# Connectors.net
KiCad netlist of a schematic drawn in Altium Designer
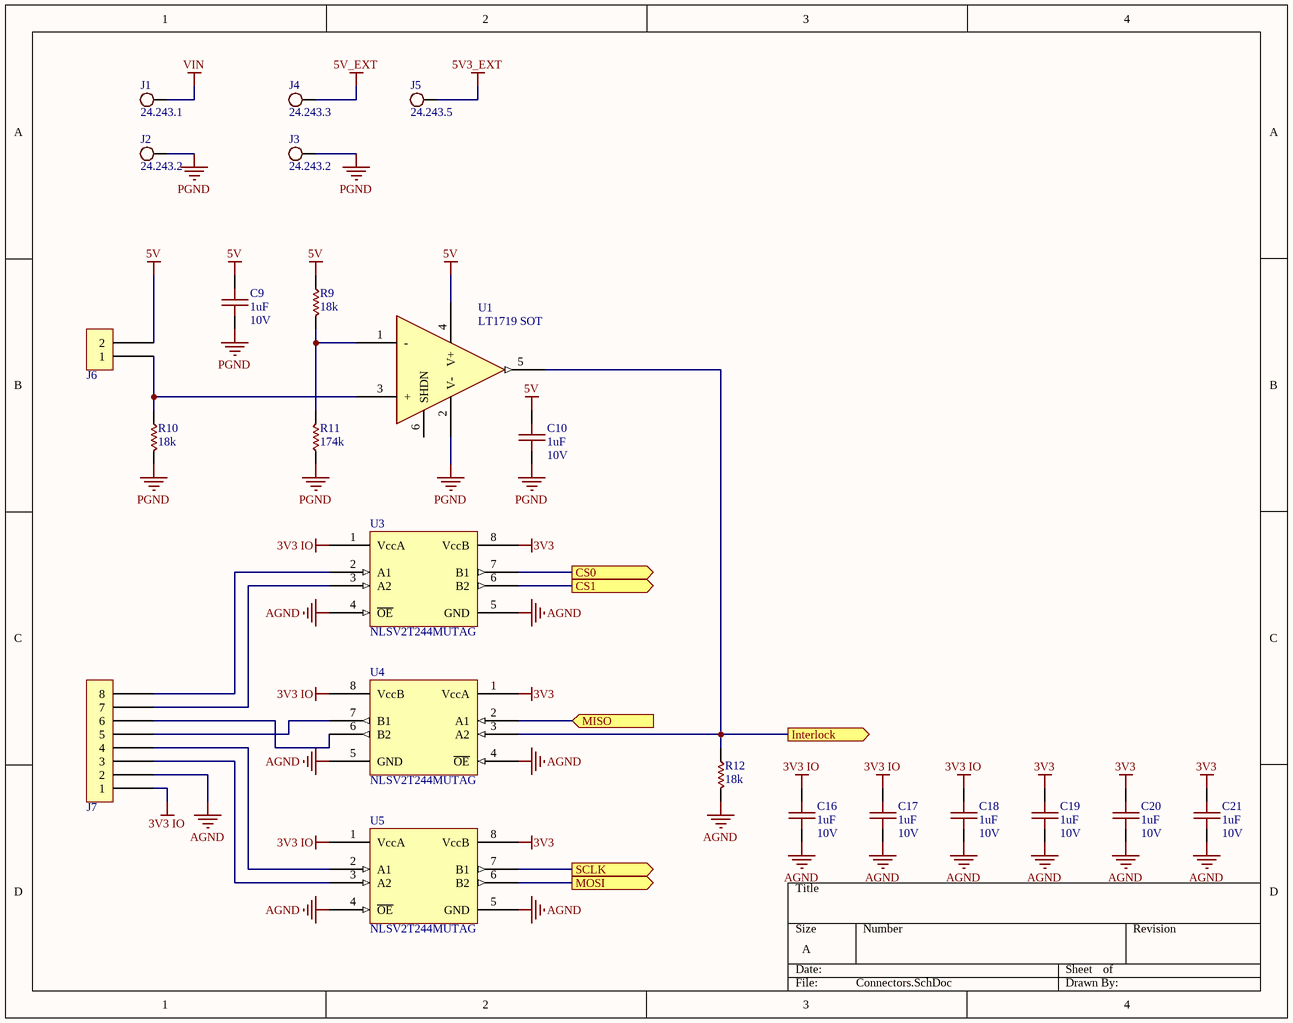
[diagram p0: Connectors.SchDoc]

(export (version "E")
  (design (tool "Eeschema 10.0.6"))
  (components
    (comp (ref "C9")
      (value "1uF")
      (footprint "0603 B")
      (description "603 Capacitor")
      (fields (field (name "VOLTAGE") "10V"))
      (libsource (lib "PSSL3") (part "CAP 0603"))
    )
    (comp (ref "C10")
      (value "1uF")
      (footprint "0603 B")
      (description "603 Capacitor")
      (fields (field (name "VOLTAGE") "10V"))
      (libsource (lib "PSSL3") (part "CAP 0603"))
    )
    (comp (ref "C16")
      (value "1uF")
      (footprint "0603 B")
      (description "603 Capacitor")
      (fields (field (name "VOLTAGE") "10V"))
      (libsource (lib "PSSL3") (part "CAP 0603"))
    )
    (comp (ref "C17")
      (value "1uF")
      (footprint "0603 B")
      (description "603 Capacitor")
      (fields (field (name "VOLTAGE") "10V"))
      (libsource (lib "PSSL3") (part "CAP 0603"))
    )
    (comp (ref "C18")
      (value "1uF")
      (footprint "0603 B")
      (description "603 Capacitor")
      (fields (field (name "VOLTAGE") "10V"))
      (libsource (lib "PSSL3") (part "CAP 0603"))
    )
    (comp (ref "C19")
      (value "1uF")
      (footprint "0603 B")
      (description "603 Capacitor")
      (fields (field (name "VOLTAGE") "10V"))
      (libsource (lib "PSSL3") (part "CAP 0603"))
    )
    (comp (ref "C20")
      (value "1uF")
      (footprint "0603 B")
      (description "603 Capacitor")
      (fields (field (name "VOLTAGE") "10V"))
      (libsource (lib "PSSL3") (part "CAP 0603"))
    )
    (comp (ref "C21")
      (value "1uF")
      (footprint "0603 B")
      (description "603 Capacitor")
      (fields (field (name "VOLTAGE") "10V"))
      (libsource (lib "PSSL3") (part "CAP 0603"))
    )
    (comp (ref "J1")
      (value "24.243.1")
      (footprint "BANANA RD")
      (description "Banana jack, PCB mount right angle")
      (libsource (lib "PSSL3") (part "BANANA RED"))
    )
    (comp (ref "J2")
      (value "24.243.2")
      (footprint "BANANA BK")
      (description "Banana jack, PCB mount right angle")
      (libsource (lib "PSSL3") (part "BANANA BLACK"))
    )
    (comp (ref "J3")
      (value "24.243.2")
      (footprint "BANANA BK")
      (description "Banana jack, PCB mount right angle")
      (libsource (lib "PSSL3") (part "BANANA BLACK"))
    )
    (comp (ref "J4")
      (value "24.243.3")
      (footprint "BANANA YL")
      (description "Banana jack, PCB mount right angle")
      (libsource (lib "PSSL3") (part "BANANA YELLOW"))
    )
    (comp (ref "J5")
      (value "24.243.5")
      (footprint "BANANA BU")
      (description "Banana jack, PCB mount right angle")
      (libsource (lib "PSSL3") (part "BANANA BLUE"))
    )
    (comp (ref "J6")
      (value "SIL02")
      (footprint "SIL02")
      (description "2.54mm Header 1x2")
      (libsource (lib "PSSL3") (part "SIL02"))
    )
    (comp (ref "J7")
      (value "SIL08")
      (footprint "SIL08")
      (description "2.54mm Header 1x6")
      (libsource (lib "PSSL3") (part "SIL08"))
    )
    (comp (ref "R9")
      (value "18k")
      (footprint "0603")
      (description "603 Resistor")
      (libsource (lib "PSSL3") (part "RES 0603"))
    )
    (comp (ref "R10")
      (value "18k")
      (footprint "0603")
      (description "603 Resistor")
      (libsource (lib "PSSL3") (part "RES 0603"))
    )
    (comp (ref "R11")
      (value "174k")
      (footprint "0603")
      (description "603 Resistor")
      (libsource (lib "PSSL3") (part "RES 0603"))
    )
    (comp (ref "R12")
      (value "18k")
      (footprint "0603")
      (description "603 Resistor")
      (libsource (lib "PSSL3") (part "RES 0603"))
    )
    (comp (ref "U1")
      (value "LT1719 SOT")
      (footprint "TSOT-23-6")
      (description "4.5ns Comparator with rail-torail output")
      (libsource (lib "PSSL3") (part "LT1719 SOT"))
    )
    (comp (ref "U3")
      (value "NLSV2T244MUTAG")
      (footprint "UDFN8")
      (description "Voltage Level Translator Unidirectional 1 Circuit 2 Channel - 8-UDFN (1.8x1.2)")
      (libsource (lib "") (part "NLSV2T244MUTAG_1"))
    )
    (comp (ref "U4")
      (value "NLSV2T244MUTAG")
      (footprint "UDFN8")
      (description "Voltage Level Translator Unidirectional 1 Circuit 2 Channel - 8-UDFN (1.8x1.2)")
      (libsource (lib "BeaconBoard") (part "NLSV2T244MUTAG"))
    )
    (comp (ref "U5")
      (value "NLSV2T244MUTAG")
      (footprint "UDFN8")
      (description "Voltage Level Translator Unidirectional 1 Circuit 2 Channel - 8-UDFN (1.8x1.2)")
      (libsource (lib "") (part "NLSV2T244MUTAG_1"))
    )
  )
  (nets
    (net (code "1") (name "/CS0") (class "Default")
      (node (ref "U3") (pin "7") (pinfunction "B1_7") (pintype "output"))
    )
    (net (code "2") (name "/CS1") (class "Default")
      (node (ref "U3") (pin "6") (pinfunction "B2_6") (pintype "output"))
    )
    (net (code "3") (name "/Interlock") (class "Default")
      (node (ref "R12") (pin "2") (pintype "passive"))
      (node (ref "U1") (pin "5") (pinfunction "OUT_5") (pintype "output"))
      (node (ref "U4") (pin "3") (pinfunction "A2_3") (pintype "input"))
    )
    (net (code "4") (name "/MISO") (class "Default")
      (node (ref "U4") (pin "2") (pinfunction "A1_2") (pintype "input"))
    )
    (net (code "5") (name "/MOSI") (class "Default")
      (node (ref "U5") (pin "6") (pinfunction "B2_6") (pintype "output"))
    )
    (net (code "6") (name "/SCLK") (class "Default")
      (node (ref "U5") (pin "7") (pinfunction "B1_7") (pintype "output"))
    )
    (net (code "7") (name "3V3") (class "Default")
      (node (ref "C19") (pin "2") (pintype "passive"))
      (node (ref "C20") (pin "2") (pintype "passive"))
      (node (ref "C21") (pin "2") (pintype "passive"))
      (node (ref "U3") (pin "8") (pinfunction "VccB_8") (pintype "power_in"))
      (node (ref "U4") (pin "1") (pinfunction "VccA_1") (pintype "power_in"))
      (node (ref "U5") (pin "8") (pinfunction "VccB_8") (pintype "power_in"))
    )
    (net (code "8") (name "3V3 IO") (class "Default")
      (node (ref "C16") (pin "2") (pintype "passive"))
      (node (ref "C17") (pin "2") (pintype "passive"))
      (node (ref "C18") (pin "2") (pintype "passive"))
      (node (ref "J7") (pin "1") (pinfunction "1_1") (pintype "passive"))
      (node (ref "U3") (pin "1") (pinfunction "VccA_1") (pintype "power_in"))
      (node (ref "U4") (pin "8") (pinfunction "VccB_8") (pintype "power_in"))
      (node (ref "U5") (pin "1") (pinfunction "VccA_1") (pintype "power_in"))
    )
    (net (code "9") (name "5V") (class "Default")
      (node (ref "C10") (pin "2") (pintype "passive"))
      (node (ref "C9") (pin "2") (pintype "passive"))
      (node (ref "J6") (pin "2") (pinfunction "2_2") (pintype "passive"))
      (node (ref "R9") (pin "2") (pintype "passive"))
      (node (ref "U1") (pin "4") (pinfunction "V+_4") (pintype "passive"))
    )
    (net (code "10") (name "5V3_EXT") (class "Default")
      (node (ref "J5") (pin "1") (pinfunction "TP_1") (pintype "passive"))
    )
    (net (code "11") (name "5V_EXT") (class "Default")
      (node (ref "J4") (pin "1") (pinfunction "TP_1") (pintype "passive"))
    )
    (net (code "12") (name "AGND") (class "Default")
      (node (ref "C16") (pin "1") (pintype "passive"))
      (node (ref "C17") (pin "1") (pintype "passive"))
      (node (ref "C18") (pin "1") (pintype "passive"))
      (node (ref "C19") (pin "1") (pintype "passive"))
      (node (ref "C20") (pin "1") (pintype "passive"))
      (node (ref "C21") (pin "1") (pintype "passive"))
      (node (ref "J7") (pin "2") (pinfunction "2_2") (pintype "passive"))
      (node (ref "R12") (pin "1") (pintype "passive"))
      (node (ref "U3") (pin "4") (pinfunction "~{OE}_4") (pintype "input"))
      (node (ref "U3") (pin "5") (pinfunction "GND_5") (pintype "power_in"))
      (node (ref "U4") (pin "4") (pinfunction "~{OE}_4") (pintype "input"))
      (node (ref "U4") (pin "5") (pinfunction "GND_5") (pintype "power_in"))
      (node (ref "U5") (pin "4") (pinfunction "~{OE}_4") (pintype "input"))
      (node (ref "U5") (pin "5") (pinfunction "GND_5") (pintype "power_in"))
    )
    (net (code "13") (name "Net-(U1-+)") (class "Default")
      (node (ref "J6") (pin "1") (pinfunction "1_1") (pintype "passive"))
      (node (ref "R10") (pin "2") (pintype "passive"))
      (node (ref "U1") (pin "3") (pinfunction "+_3") (pintype "tri_state"))
    )
    (net (code "14") (name "Net-(U1--)") (class "Default")
      (node (ref "R11") (pin "1") (pintype "passive"))
      (node (ref "R9") (pin "1") (pintype "passive"))
      (node (ref "U1") (pin "1") (pinfunction "-_1") (pintype "tri_state"))
    )
    (net (code "15") (name "Net-(U3-A1)") (class "Default")
      (node (ref "J7") (pin "8") (pinfunction "8_8") (pintype "passive"))
      (node (ref "U3") (pin "2") (pinfunction "A1_2") (pintype "input"))
    )
    (net (code "16") (name "Net-(U3-A2)") (class "Default")
      (node (ref "J7") (pin "7") (pinfunction "7_7") (pintype "passive"))
      (node (ref "U3") (pin "3") (pinfunction "A2_3") (pintype "input"))
    )
    (net (code "17") (name "Net-(U4-B1)") (class "Default")
      (node (ref "J7") (pin "5") (pinfunction "5_5") (pintype "passive"))
      (node (ref "U4") (pin "7") (pinfunction "B1_7") (pintype "output"))
    )
    (net (code "18") (name "Net-(U4-B2)") (class "Default")
      (node (ref "J7") (pin "6") (pinfunction "6_6") (pintype "passive"))
      (node (ref "U4") (pin "6") (pinfunction "B2_6") (pintype "output"))
    )
    (net (code "19") (name "Net-(U5-A1)") (class "Default")
      (node (ref "J7") (pin "4") (pinfunction "4_4") (pintype "passive"))
      (node (ref "U5") (pin "2") (pinfunction "A1_2") (pintype "input"))
    )
    (net (code "20") (name "Net-(U5-A2)") (class "Default")
      (node (ref "J7") (pin "3") (pinfunction "3_3") (pintype "passive"))
      (node (ref "U5") (pin "3") (pinfunction "A2_3") (pintype "input"))
    )
    (net (code "21") (name "PGND") (class "Default")
      (node (ref "C10") (pin "1") (pintype "passive"))
      (node (ref "C9") (pin "1") (pintype "passive"))
      (node (ref "J2") (pin "1") (pinfunction "TP_1") (pintype "passive"))
      (node (ref "J3") (pin "1") (pinfunction "TP_1") (pintype "passive"))
      (node (ref "R10") (pin "1") (pintype "passive"))
      (node (ref "R11") (pin "2") (pintype "passive"))
      (node (ref "U1") (pin "2") (pinfunction "V-_2") (pintype "passive"))
    )
    (net (code "22") (name "VIN") (class "Default")
      (node (ref "J1") (pin "1") (pinfunction "TP_1") (pintype "passive"))
    )
    (net (code "23") (name "unconnected-(U1-SHDN-Pad6)") (class "Default")
      (node (ref "U1") (pin "6") (pinfunction "SHDN_6") (pintype "passive"))
    )
  )
)
